# heart_necklace.net
KiCad netlist of a schematic drawn in EAGLE
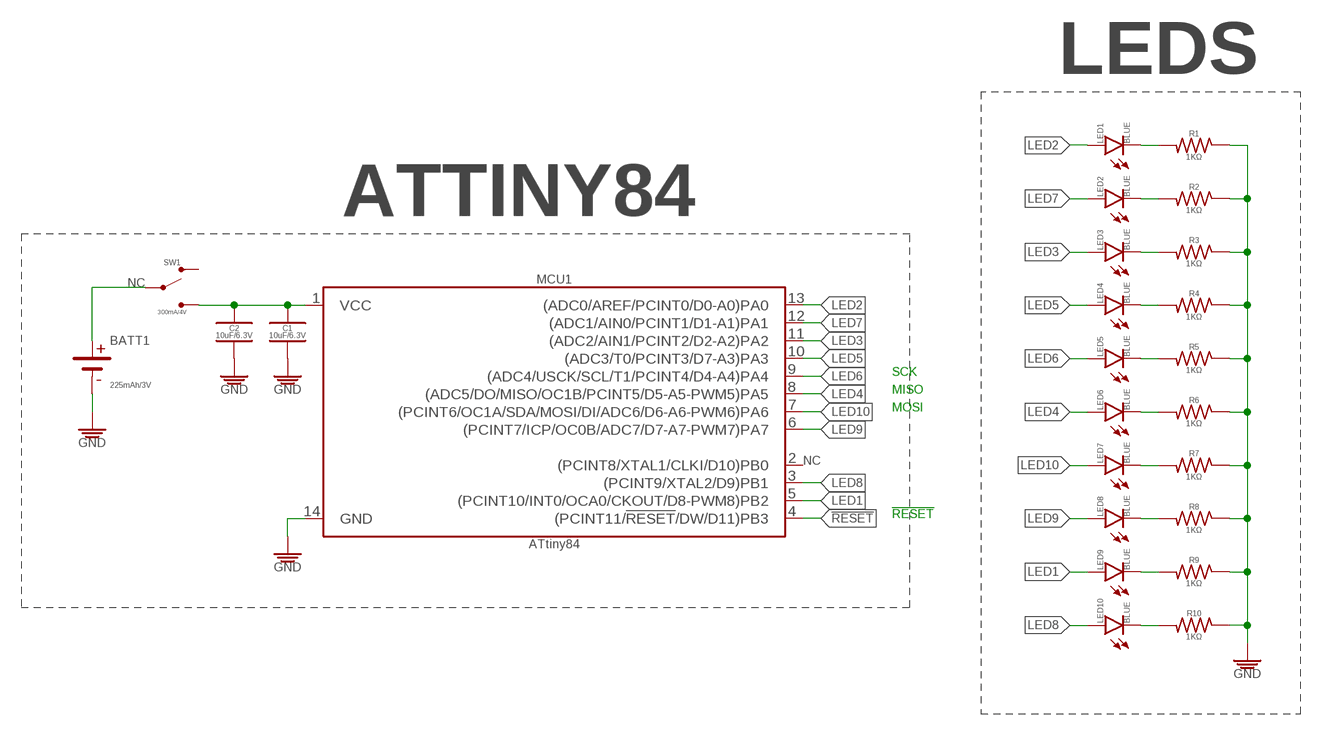
[diagram p0: schematic, sheet 1]

(export (version "E")
  (design (tool "Eeschema 10.0.6"))
  (components
    (comp (ref "BATT1")
      (value "225mAh/3V")
      (footprint "eagle-import:CR-2032")
      (fields (field (name "MFR") "Panasonic - BSG") (field (name "MPN") "CR2032"))
      (libsource (lib "eagle-import") (part "BATTERY_COIN-CELL_SMD_3V_20MM"))
    )
    (comp (ref "C1")
      (value "10uF/6.3V")
      (footprint "eagle-import:CAPC1005X55_SMD-0402")
      (fields (field (name "MFR") "Taiyo Yuden") (field (name "MPN") "JMK105CBJ106MV-F"))
      (libsource (lib "eagle-import") (part "10UF_CER_SMD-0402_6.3V-20%"))
    )
    (comp (ref "C2")
      (value "10uF/6.3V")
      (footprint "eagle-import:CAPC1005X55_SMD-0402")
      (fields (field (name "MFR") "Taiyo Yuden") (field (name "MPN") "JMK105CBJ106MV-F"))
      (libsource (lib "eagle-import") (part "10UF_CER_SMD-0402_6.3V-20%"))
    )
    (comp (ref "LED1")
      (value "BLUE")
      (footprint "eagle-import:LEDC2012X120")
      (fields (field (name "MFR") "Lite-On Inc.") (field (name "MPN") "LTST-C170TBKT"))
      (libsource (lib "eagle-import") (part "LED_SMD-0805_DISCRETE_BLUE"))
    )
    (comp (ref "LED2")
      (value "BLUE")
      (footprint "eagle-import:LEDC2012X120")
      (fields (field (name "MFR") "Lite-On Inc.") (field (name "MPN") "LTST-C170TBKT"))
      (libsource (lib "eagle-import") (part "LED_SMD-0805_DISCRETE_BLUE"))
    )
    (comp (ref "LED3")
      (value "BLUE")
      (footprint "eagle-import:LEDC2012X120")
      (fields (field (name "MFR") "Lite-On Inc.") (field (name "MPN") "LTST-C170TBKT"))
      (libsource (lib "eagle-import") (part "LED_SMD-0805_DISCRETE_BLUE"))
    )
    (comp (ref "LED4")
      (value "BLUE")
      (footprint "eagle-import:LEDC2012X120")
      (fields (field (name "MFR") "Lite-On Inc.") (field (name "MPN") "LTST-C170TBKT"))
      (libsource (lib "eagle-import") (part "LED_SMD-0805_DISCRETE_BLUE"))
    )
    (comp (ref "LED5")
      (value "BLUE")
      (footprint "eagle-import:LEDC2012X120")
      (fields (field (name "MFR") "Lite-On Inc.") (field (name "MPN") "LTST-C170TBKT"))
      (libsource (lib "eagle-import") (part "LED_SMD-0805_DISCRETE_BLUE"))
    )
    (comp (ref "LED6")
      (value "BLUE")
      (footprint "eagle-import:LEDC2012X120")
      (fields (field (name "MFR") "Lite-On Inc.") (field (name "MPN") "LTST-C170TBKT"))
      (libsource (lib "eagle-import") (part "LED_SMD-0805_DISCRETE_BLUE"))
    )
    (comp (ref "LED7")
      (value "BLUE")
      (footprint "eagle-import:LEDC2012X120")
      (fields (field (name "MFR") "Lite-On Inc.") (field (name "MPN") "LTST-C170TBKT"))
      (libsource (lib "eagle-import") (part "LED_SMD-0805_DISCRETE_BLUE"))
    )
    (comp (ref "LED8")
      (value "BLUE")
      (footprint "eagle-import:LEDC2012X120")
      (fields (field (name "MFR") "Lite-On Inc.") (field (name "MPN") "LTST-C170TBKT"))
      (libsource (lib "eagle-import") (part "LED_SMD-0805_DISCRETE_BLUE"))
    )
    (comp (ref "LED9")
      (value "BLUE")
      (footprint "eagle-import:LEDC2012X120")
      (fields (field (name "MFR") "Lite-On Inc.") (field (name "MPN") "LTST-C170TBKT"))
      (libsource (lib "eagle-import") (part "LED_SMD-0805_DISCRETE_BLUE"))
    )
    (comp (ref "LED10")
      (value "BLUE")
      (footprint "eagle-import:LEDC2012X120")
      (fields (field (name "MFR") "Lite-On Inc.") (field (name "MPN") "LTST-C170TBKT"))
      (libsource (lib "eagle-import") (part "LED_SMD-0805_DISCRETE_BLUE"))
    )
    (comp (ref "MCU1")
      (value "ATtiny84")
      (footprint "eagle-import:SOIC127P599X175-14_SOIC-14_NO-SILK")
      (fields (field (name "MFR") "Microchip Technology") (field (name "MPN") "ATTINY84A-SSU"))
      (libsource (lib "eagle-import") (part "ATTINY84_SOIC-14_NO_SILK"))
    )
    (comp (ref "R1")
      (value "1KΩ")
      (footprint "eagle-import:RESISTOR_SMD-805")
      (fields
        (field (name "MFR") "Yageo")
        (field (name "MPN") "RC0805JR-071KL ")
        (field (name "CREATOR") "Kenmei")
      )
      (libsource (lib "eagle-import") (part "1KΩ_SMD-0805_1/8W-5%"))
    )
    (comp (ref "R2")
      (value "1KΩ")
      (footprint "eagle-import:RESISTOR_SMD-805")
      (fields
        (field (name "MFR") "Yageo")
        (field (name "MPN") "RC0805JR-071KL ")
        (field (name "CREATOR") "Kenmei")
      )
      (libsource (lib "eagle-import") (part "1KΩ_SMD-0805_1/8W-5%"))
    )
    (comp (ref "R3")
      (value "1KΩ")
      (footprint "eagle-import:RESISTOR_SMD-805")
      (fields
        (field (name "MFR") "Yageo")
        (field (name "MPN") "RC0805JR-071KL ")
        (field (name "CREATOR") "Kenmei")
      )
      (libsource (lib "eagle-import") (part "1KΩ_SMD-0805_1/8W-5%"))
    )
    (comp (ref "R4")
      (value "1KΩ")
      (footprint "eagle-import:RESISTOR_SMD-805")
      (fields
        (field (name "MFR") "Yageo")
        (field (name "MPN") "RC0805JR-071KL ")
        (field (name "CREATOR") "Kenmei")
      )
      (libsource (lib "eagle-import") (part "1KΩ_SMD-0805_1/8W-5%"))
    )
    (comp (ref "R5")
      (value "1KΩ")
      (footprint "eagle-import:RESISTOR_SMD-805")
      (fields
        (field (name "MFR") "Yageo")
        (field (name "MPN") "RC0805JR-071KL ")
        (field (name "CREATOR") "Kenmei")
      )
      (libsource (lib "eagle-import") (part "1KΩ_SMD-0805_1/8W-5%"))
    )
    (comp (ref "R6")
      (value "1KΩ")
      (footprint "eagle-import:RESISTOR_SMD-805")
      (fields
        (field (name "MFR") "Yageo")
        (field (name "MPN") "RC0805JR-071KL ")
        (field (name "CREATOR") "Kenmei")
      )
      (libsource (lib "eagle-import") (part "1KΩ_SMD-0805_1/8W-5%"))
    )
    (comp (ref "R7")
      (value "1KΩ")
      (footprint "eagle-import:RESISTOR_SMD-805")
      (fields
        (field (name "MFR") "Yageo")
        (field (name "MPN") "RC0805JR-071KL ")
        (field (name "CREATOR") "Kenmei")
      )
      (libsource (lib "eagle-import") (part "1KΩ_SMD-0805_1/8W-5%"))
    )
    (comp (ref "R8")
      (value "1KΩ")
      (footprint "eagle-import:RESISTOR_SMD-805")
      (fields
        (field (name "MFR") "Yageo")
        (field (name "MPN") "RC0805JR-071KL ")
        (field (name "CREATOR") "Kenmei")
      )
      (libsource (lib "eagle-import") (part "1KΩ_SMD-0805_1/8W-5%"))
    )
    (comp (ref "R9")
      (value "1KΩ")
      (footprint "eagle-import:RESISTOR_SMD-805")
      (fields
        (field (name "MFR") "Yageo")
        (field (name "MPN") "RC0805JR-071KL ")
        (field (name "CREATOR") "Kenmei")
      )
      (libsource (lib "eagle-import") (part "1KΩ_SMD-0805_1/8W-5%"))
    )
    (comp (ref "R10")
      (value "1KΩ")
      (footprint "eagle-import:RESISTOR_SMD-805")
      (fields
        (field (name "MFR") "Yageo")
        (field (name "MPN") "RC0805JR-071KL ")
        (field (name "CREATOR") "Kenmei")
      )
      (libsource (lib "eagle-import") (part "1KΩ_SMD-0805_1/8W-5%"))
    )
    (comp (ref "SW1")
      (value "300mA/4V")
      (footprint "eagle-import:SW_SLIDE_SPDT_RA_SMD_4V_300MA_6.7L-2.6W")
      (fields
        (field (name "MFR") "APEM Inc.")
        (field (name "MPN") "MA12RTR")
        (field (name "CREATOR") "MrSwirlyEyes")
      )
      (libsource (lib "eagle-import") (part "SWITCH_SPDT_RA_SMD_300MA-4V_6.7L-2.6W"))
    )
  )
  (nets
    (net (code "1") (name "/~{RESET}") (class "Default")
      (node (ref "MCU1") (pin "4") (pinfunction "(PCINT11/~{RESET}/DW/D11)PB3_4") (pintype "bidirectional"))
    )
    (net (code "2") (name "GND") (class "Default")
      (node (ref "BATT1") (pin "-") (pinfunction "-_-") (pintype "bidirectional"))
      (node (ref "C1") (pin "2") (pinfunction "2_2") (pintype "passive"))
      (node (ref "C2") (pin "2") (pinfunction "2_2") (pintype "passive"))
      (node (ref "MCU1") (pin "14") (pinfunction "GND_14") (pintype "passive"))
      (node (ref "R1") (pin "1") (pinfunction "1_1") (pintype "passive"))
      (node (ref "R10") (pin "1") (pinfunction "1_1") (pintype "passive"))
      (node (ref "R2") (pin "1") (pinfunction "1_1") (pintype "passive"))
      (node (ref "R3") (pin "1") (pinfunction "1_1") (pintype "passive"))
      (node (ref "R4") (pin "1") (pinfunction "1_1") (pintype "passive"))
      (node (ref "R5") (pin "1") (pinfunction "1_1") (pintype "passive"))
      (node (ref "R6") (pin "1") (pinfunction "1_1") (pintype "passive"))
      (node (ref "R7") (pin "1") (pinfunction "1_1") (pintype "passive"))
      (node (ref "R8") (pin "1") (pinfunction "1_1") (pintype "passive"))
      (node (ref "R9") (pin "1") (pinfunction "1_1") (pintype "passive"))
    )
    (net (code "3") (name "LED1") (class "Default")
      (node (ref "LED9") (pin "A") (pinfunction "A_A") (pintype "passive"))
      (node (ref "MCU1") (pin "5") (pinfunction "(PCINT10/INT0/OCA0/CKOUT/D8-PWM8)PB2_5") (pintype "bidirectional"))
    )
    (net (code "4") (name "LED2") (class "Default")
      (node (ref "LED1") (pin "A") (pinfunction "A_A") (pintype "passive"))
      (node (ref "MCU1") (pin "13") (pinfunction "(ADC0/AREF/PCINT0/D0-A0)PA0_13") (pintype "bidirectional"))
    )
    (net (code "5") (name "LED3") (class "Default")
      (node (ref "LED3") (pin "A") (pinfunction "A_A") (pintype "passive"))
      (node (ref "MCU1") (pin "11") (pinfunction "(ADC2/AIN1/PCINT2/D2-A2)PA2_11") (pintype "bidirectional"))
    )
    (net (code "6") (name "LED4") (class "Default")
      (node (ref "LED6") (pin "A") (pinfunction "A_A") (pintype "passive"))
      (node (ref "MCU1") (pin "8") (pinfunction "(ADC5/DO/MISO/OC1B/PCINT5/D5-A5-PWM5)PA5_8") (pintype "bidirectional"))
    )
    (net (code "7") (name "LED5") (class "Default")
      (node (ref "LED4") (pin "A") (pinfunction "A_A") (pintype "passive"))
      (node (ref "MCU1") (pin "10") (pinfunction "(ADC3/T0/PCINT3/D7-A3)PA3_10") (pintype "bidirectional"))
    )
    (net (code "8") (name "LED6") (class "Default")
      (node (ref "LED5") (pin "A") (pinfunction "A_A") (pintype "passive"))
      (node (ref "MCU1") (pin "9") (pinfunction "(ADC4/USCK/SCL/T1/PCINT4/D4-A4)PA4_9") (pintype "bidirectional"))
    )
    (net (code "9") (name "LED7") (class "Default")
      (node (ref "LED2") (pin "A") (pinfunction "A_A") (pintype "passive"))
      (node (ref "MCU1") (pin "12") (pinfunction "(ADC1/AIN0/PCINT1/D1-A1)PA1_12") (pintype "bidirectional"))
    )
    (net (code "10") (name "LED8") (class "Default")
      (node (ref "LED10") (pin "A") (pinfunction "A_A") (pintype "passive"))
      (node (ref "MCU1") (pin "3") (pinfunction "(PCINT9/XTAL2/D9)PB1_3") (pintype "bidirectional"))
    )
    (net (code "11") (name "LED9") (class "Default")
      (node (ref "LED8") (pin "A") (pinfunction "A_A") (pintype "passive"))
      (node (ref "MCU1") (pin "6") (pinfunction "(PCINT7/ICP/OC0B/ADC7/D7-A7-PWM7)PA7_6") (pintype "bidirectional"))
    )
    (net (code "12") (name "LED10") (class "Default")
      (node (ref "LED7") (pin "A") (pinfunction "A_A") (pintype "passive"))
      (node (ref "MCU1") (pin "7") (pinfunction "(PCINT6/OC1A/SDA/MOSI/DI/ADC6/D6-A6-PWM6)PA6_7") (pintype "bidirectional"))
    )
    (net (code "13") (name "Net-(LED1-PadK)") (class "Default")
      (node (ref "LED1") (pin "K") (pinfunction "K_K") (pintype "passive"))
      (node (ref "R1") (pin "2") (pinfunction "2_2") (pintype "passive"))
    )
    (net (code "14") (name "Net-(LED2-PadK)") (class "Default")
      (node (ref "LED2") (pin "K") (pinfunction "K_K") (pintype "passive"))
      (node (ref "R2") (pin "2") (pinfunction "2_2") (pintype "passive"))
    )
    (net (code "15") (name "Net-(LED3-PadK)") (class "Default")
      (node (ref "LED3") (pin "K") (pinfunction "K_K") (pintype "passive"))
      (node (ref "R3") (pin "2") (pinfunction "2_2") (pintype "passive"))
    )
    (net (code "16") (name "Net-(LED4-PadK)") (class "Default")
      (node (ref "LED4") (pin "K") (pinfunction "K_K") (pintype "passive"))
      (node (ref "R4") (pin "2") (pinfunction "2_2") (pintype "passive"))
    )
    (net (code "17") (name "Net-(LED5-PadK)") (class "Default")
      (node (ref "LED5") (pin "K") (pinfunction "K_K") (pintype "passive"))
      (node (ref "R5") (pin "2") (pinfunction "2_2") (pintype "passive"))
    )
    (net (code "18") (name "Net-(LED6-PadK)") (class "Default")
      (node (ref "LED6") (pin "K") (pinfunction "K_K") (pintype "passive"))
      (node (ref "R6") (pin "2") (pinfunction "2_2") (pintype "passive"))
    )
    (net (code "19") (name "Net-(LED7-PadK)") (class "Default")
      (node (ref "LED7") (pin "K") (pinfunction "K_K") (pintype "passive"))
      (node (ref "R7") (pin "2") (pinfunction "2_2") (pintype "passive"))
    )
    (net (code "20") (name "Net-(LED8-PadK)") (class "Default")
      (node (ref "LED8") (pin "K") (pinfunction "K_K") (pintype "passive"))
      (node (ref "R8") (pin "2") (pinfunction "2_2") (pintype "passive"))
    )
    (net (code "21") (name "Net-(LED9-PadK)") (class "Default")
      (node (ref "LED9") (pin "K") (pinfunction "K_K") (pintype "passive"))
      (node (ref "R9") (pin "2") (pinfunction "2_2") (pintype "passive"))
    )
    (net (code "22") (name "Net-(LED10-PadK)") (class "Default")
      (node (ref "LED10") (pin "K") (pinfunction "K_K") (pintype "passive"))
      (node (ref "R10") (pin "2") (pinfunction "2_2") (pintype "passive"))
    )
    (net (code "23") (name "Net-(MCU1-VCC)") (class "Default")
      (node (ref "C1") (pin "1") (pinfunction "1_1") (pintype "passive"))
      (node (ref "C2") (pin "1") (pinfunction "1_1") (pintype "passive"))
      (node (ref "MCU1") (pin "1") (pinfunction "VCC_1") (pintype "passive"))
      (node (ref "SW1") (pin "3") (pinfunction "S2_3") (pintype "passive"))
    )
    (net (code "24") (name "Net-(SW1-P)") (class "Default")
      (node (ref "BATT1") (pin "+_1") (pinfunction "+_+_1") (pintype "bidirectional"))
      (node (ref "BATT1") (pin "+_2") (pinfunction "+_+_2") (pintype "bidirectional"))
      (node (ref "SW1") (pin "2") (pinfunction "P_2") (pintype "passive"))
    )
    (net (code "25") (name "unconnected-(MCU1-(PCINT8{slash}XTAL1{slash}CLKI{slash}D10)PB0-Pad2)") (class "Default")
      (node (ref "MCU1") (pin "2") (pinfunction "(PCINT8/XTAL1/CLKI/D10)PB0_2") (pintype "bidirectional"))
    )
    (net (code "26") (name "unconnected-(SW1-S1-Pad1)") (class "Default")
      (node (ref "SW1") (pin "1") (pinfunction "S1_1") (pintype "passive"))
    )
  )
)
